# EEZ_AUX_PS_r4B41.net
KiCad netlist of a schematic drawn in EAGLE
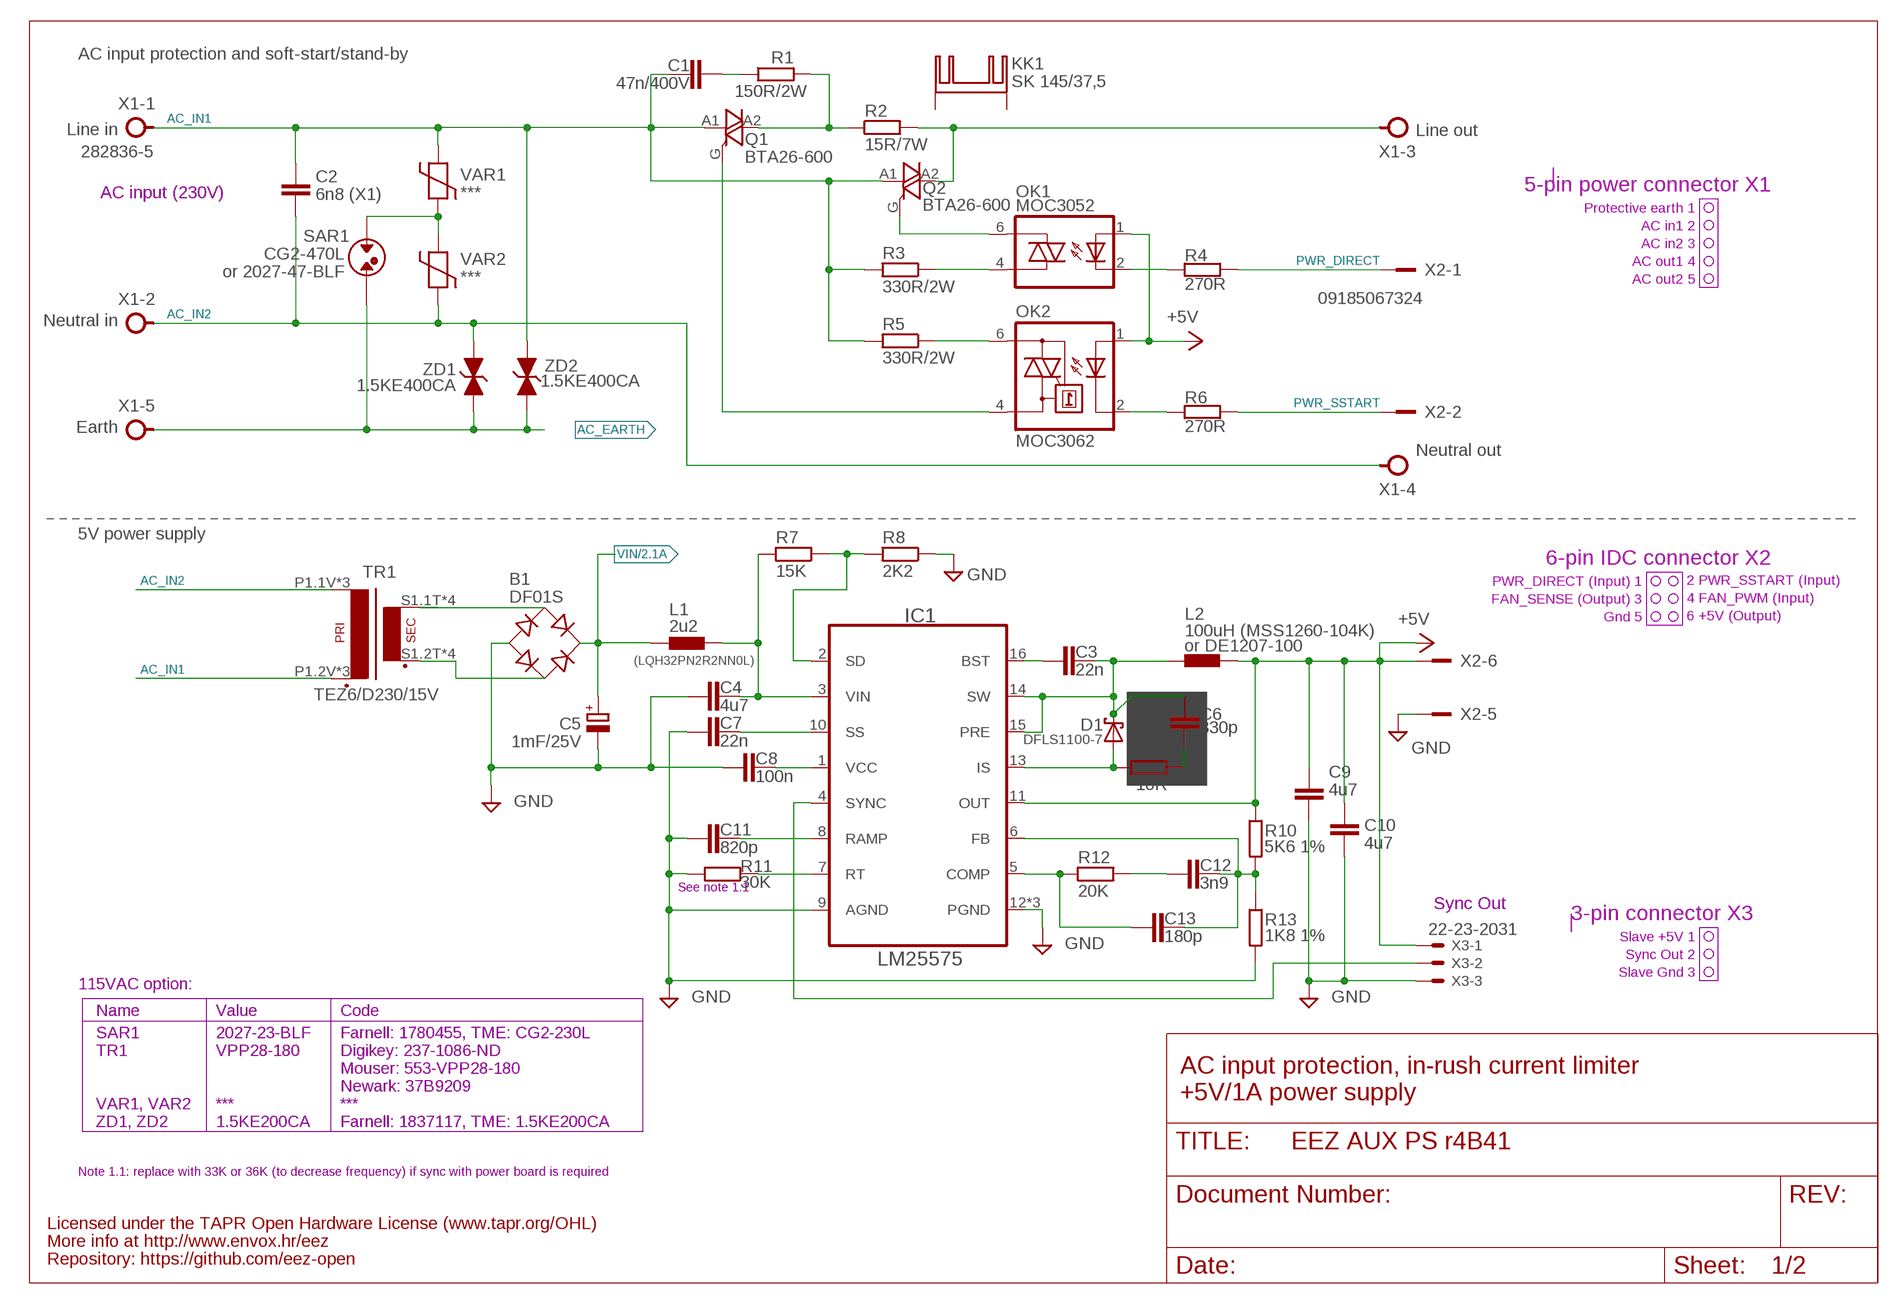
[diagram p0: schematic, sheet 1]
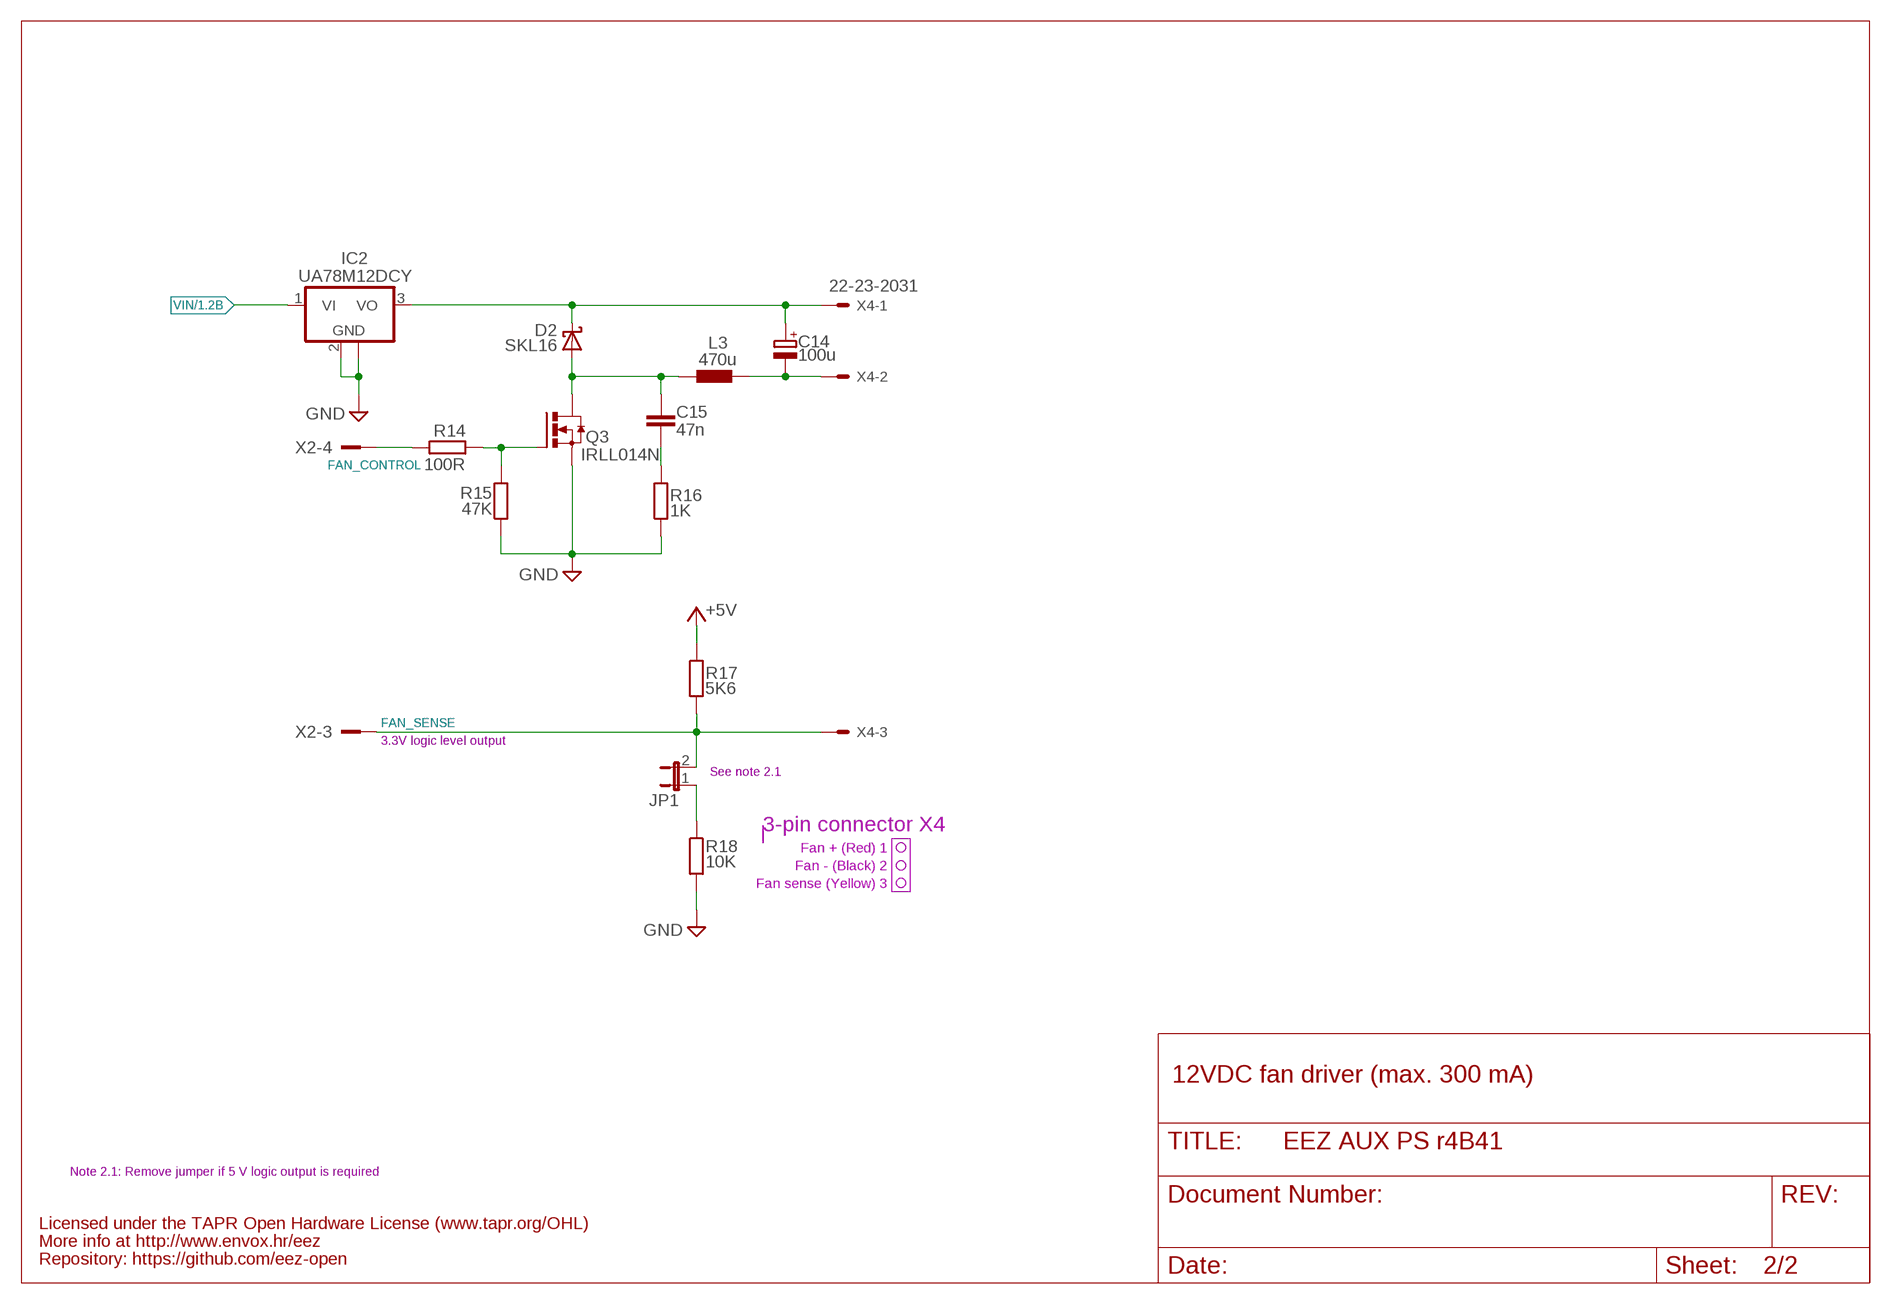
[diagram p1: schematic, sheet 2]

(export (version "E")
  (design (tool "Eeschema 10.0.6"))
  (components
    (comp (ref "C14")
      (value "100u")
      (footprint "eagle-import:CAPAE660X610N")
      (libsource (lib "eagle-import") (part "ECAPPANASONIC_H"))
    )
    (comp (ref "C15")
      (value "47n")
      (footprint "eagle-import:C0805")
      (libsource (lib "eagle-import") (part "C-EUC0805"))
    )
    (comp (ref "D2")
      (value "SKL16")
      (footprint "eagle-import:SOD123")
      (libsource (lib "eagle-import") (part "SCHOTTKYSOD123"))
    )
    (comp (ref "IC2")
      (value "UA78M12DCY")
      (footprint "eagle-import:SOT230P700X180-4N")
      (libsource (lib "eagle-import") (part "UA78MDCY"))
    )
    (comp (ref "JP1")
      (value "JP1E")
      (footprint "eagle-import:JP1")
      (libsource (lib "eagle-import") (part "JP1E"))
    )
    (comp (ref "L3")
      (value "470u")
      (footprint "eagle-import:DE0704")
      (libsource (lib "eagle-import") (part "DE0704"))
    )
    (comp (ref "Q3")
      (value "IRLL014N")
      (footprint "eagle-import:SOT223")
      (libsource (lib "eagle-import") (part "N-HEXFET-2D_?-SOT232IRLL014N"))
    )
    (comp (ref "R14")
      (value "100R")
      (footprint "eagle-import:R0805")
      (libsource (lib "eagle-import") (part "R-EU_R0805"))
    )
    (comp (ref "R15")
      (value "47K")
      (footprint "eagle-import:R0805")
      (libsource (lib "eagle-import") (part "R-EU_R0805"))
    )
    (comp (ref "R16")
      (value "1K")
      (footprint "eagle-import:R0805")
      (libsource (lib "eagle-import") (part "R-EU_R0805"))
    )
    (comp (ref "R17")
      (value "5K6")
      (footprint "eagle-import:R0805")
      (libsource (lib "eagle-import") (part "R-EU_R0805"))
    )
    (comp (ref "R18")
      (value "10K")
      (footprint "eagle-import:R0805")
      (libsource (lib "eagle-import") (part "R-EU_R0805"))
    )
    (comp (ref "X2")
      (value "09185067324")
      (footprint "eagle-import:IDC-6PIN")
      (libsource (lib "eagle-import") (part "IDC-6PIN"))
    )
    (comp (ref "X4")
      (value "22-23-2031")
      (footprint "eagle-import:22-23-2031")
      (fields (field (name "MF") "MOLEX"))
      (libsource (lib "eagle-import") (part "22-23-2031"))
    )
    (comp (ref "B1")
      (value "DF01S")
      (footprint "eagle-import:DFS")
      (libsource (lib "eagle-import") (part "DFS01"))
    )
    (comp (ref "C1")
      (value "47n/400V")
      (footprint "eagle-import:C075-052X106")
      (libsource (lib "eagle-import") (part "C-EU075-052X106"))
    )
    (comp (ref "C2")
      (value "6n8 (X1)")
      (footprint "eagle-import:C102-064X133")
      (libsource (lib "eagle-import") (part "C-EU102-064X133"))
    )
    (comp (ref "C3")
      (value "22n")
      (footprint "eagle-import:C0805")
      (libsource (lib "eagle-import") (part "C-EUC0805"))
    )
    (comp (ref "C4")
      (value "4u7")
      (footprint "eagle-import:C1210")
      (libsource (lib "eagle-import") (part "C-EUC1210"))
    )
    (comp (ref "C5")
      (value "1mF/25V")
      (footprint "eagle-import:ECAP5_10.5")
      (libsource (lib "eagle-import") (part "ECAP5G_10.5MM"))
    )
    (comp (ref "C6")
      (value "330p")
      (footprint "eagle-import:C0805")
      (libsource (lib "eagle-import") (part "C-EUC0805"))
    )
    (comp (ref "C7")
      (value "22n")
      (footprint "eagle-import:C0805")
      (libsource (lib "eagle-import") (part "C-EUC0805"))
    )
    (comp (ref "C8")
      (value "100n")
      (footprint "eagle-import:C0805")
      (libsource (lib "eagle-import") (part "C-EUC0805"))
    )
    (comp (ref "C9")
      (value "4u7")
      (footprint "eagle-import:C1210")
      (libsource (lib "eagle-import") (part "C-EUC1210"))
    )
    (comp (ref "C10")
      (value "4u7")
      (footprint "eagle-import:C1210")
      (libsource (lib "eagle-import") (part "C-EUC1210"))
    )
    (comp (ref "C11")
      (value "820p")
      (footprint "eagle-import:C0805")
      (libsource (lib "eagle-import") (part "C-EUC0805"))
    )
    (comp (ref "C12")
      (value "3n9")
      (footprint "eagle-import:C0805")
      (libsource (lib "eagle-import") (part "C-EUC0805"))
    )
    (comp (ref "C13")
      (value "180p")
      (footprint "eagle-import:C0805")
      (libsource (lib "eagle-import") (part "C-EUC0805"))
    )
    (comp (ref "D1")
      (value "DFLS1100-7")
      (footprint "eagle-import:SOD123")
      (libsource (lib "eagle-import") (part "SCHOTTKYSOD123"))
    )
    (comp (ref "IC1")
      (value "LM25575")
      (footprint "eagle-import:SOP65P640X110-17N_HOLE")
      (libsource (lib "eagle-import") (part "LM(2)5575"))
    )
    (comp (ref "KK1")
      (value "SK 145/37,5")
      (footprint "eagle-import:SK145")
      (libsource (lib "eagle-import") (part "SK145"))
    )
    (comp (ref "L1")
      (value "2u2")
      (footprint "eagle-import:L1210")
      (libsource (lib "eagle-import") (part "L1210"))
    )
    (comp (ref "L2")
      (value "100uH (MSS1260-104K)")
      (footprint "eagle-import:MSS1278")
      (libsource (lib "eagle-import") (part "COILCRAFT_MSS1278"))
    )
    (comp (ref "OK1")
      (value "MOC3052")
      (footprint "eagle-import:DIL6-SMD")
      (libsource (lib "eagle-import") (part "MOC305X"))
    )
    (comp (ref "OK2")
      (value "MOC3062")
      (footprint "eagle-import:DIL6-SMD")
      (fields
        (field (name "MF") "FAIRCHILD SEMICONDUCTOR")
        (field (name "MPN") "MOC3033S-M")
        (field (name "MF_1") "FAIRCHILD SEMICONDUCTOR")
        (field (name "MPN_1") "MOC3033S-M")
        (field (name "OC_FARNELL") "unknown")
        (field (name "OC_NEWARK") "05C2878")
      )
      (libsource (lib "eagle-import") (part "MOC30S33"))
    )
    (comp (ref "Q1")
      (value "BTA26-600")
      (footprint "eagle-import:TOP3S-1")
      (libsource (lib "eagle-import") (part "BTA26-V"))
    )
    (comp (ref "Q2")
      (value "BTA26-600")
      (footprint "eagle-import:TOP3S-1")
      (libsource (lib "eagle-import") (part "BTA26-V"))
    )
    (comp (ref "R1")
      (value "150R/2W")
      (footprint "eagle-import:R2512")
      (libsource (lib "eagle-import") (part "R-EU_R2512"))
    )
    (comp (ref "R2")
      (value "15R/7W")
      (footprint "eagle-import:R_0913")
      (libsource (lib "eagle-import") (part "R_EU7W"))
    )
    (comp (ref "R3")
      (value "330R/2W")
      (footprint "eagle-import:R2512")
      (libsource (lib "eagle-import") (part "R-EU_R2512"))
    )
    (comp (ref "R4")
      (value "270R")
      (footprint "eagle-import:R0805")
      (libsource (lib "eagle-import") (part "R-EU_R0805"))
    )
    (comp (ref "R5")
      (value "330R/2W")
      (footprint "eagle-import:R2512")
      (libsource (lib "eagle-import") (part "R-EU_R2512"))
    )
    (comp (ref "R6")
      (value "270R")
      (footprint "eagle-import:R0805")
      (libsource (lib "eagle-import") (part "R-EU_R0805"))
    )
    (comp (ref "R7")
      (value "15K")
      (footprint "eagle-import:R0805")
      (libsource (lib "eagle-import") (part "R-EU_R0805"))
    )
    (comp (ref "R8")
      (value "2K2")
      (footprint "eagle-import:R0805")
      (libsource (lib "eagle-import") (part "R-EU_R0805"))
    )
    (comp (ref "R9")
      (value "10R")
      (footprint "eagle-import:R1206")
      (libsource (lib "eagle-import") (part "R-EU_R1206"))
    )
    (comp (ref "R10")
      (value "5K6 1%")
      (footprint "eagle-import:R0805")
      (libsource (lib "eagle-import") (part "R-EU_R0805"))
    )
    (comp (ref "R11")
      (value "30K")
      (footprint "eagle-import:R0805")
      (libsource (lib "eagle-import") (part "R-EU_R0805"))
    )
    (comp (ref "R12")
      (value "20K")
      (footprint "eagle-import:R0805")
      (libsource (lib "eagle-import") (part "R-EU_R0805"))
    )
    (comp (ref "R13")
      (value "1K8 1%")
      (footprint "eagle-import:R0805")
      (libsource (lib "eagle-import") (part "R-EU_R0805"))
    )
    (comp (ref "SAR1")
      (value "CG2-470L")
      (footprint "eagle-import:SAR")
      (libsource (lib "eagle-import") (part "SAR"))
    )
    (comp (ref "TR1")
      (value "TEZ6/D230/15V")
      (footprint "eagle-import:PCB_TRAFO6VA_TEZ+VPP")
      (libsource (lib "eagle-import") (part "PCB_TRAFO6VA_TEZ+VPP"))
    )
    (comp (ref "VAR1")
      (value "***")
      (footprint "eagle-import:VARISTOR")
      (libsource (lib "eagle-import") (part "VARISTOR"))
    )
    (comp (ref "VAR2")
      (value "***")
      (footprint "eagle-import:VARISTOR")
      (libsource (lib "eagle-import") (part "VARISTOR"))
    )
    (comp (ref "X1")
      (value "282836-5")
      (footprint "eagle-import:TBLOCK5.0_5")
      (libsource (lib "eagle-import") (part "TBLOCK5.0_5A"))
    )
    (comp (ref "X3")
      (value "22-23-2031")
      (footprint "eagle-import:22-23-2031")
      (fields (field (name "MF") "MOLEX"))
      (libsource (lib "eagle-import") (part "22-23-2031"))
    )
    (comp (ref "ZD1")
      (value "1.5KE400CA")
      (footprint "eagle-import:DO201-BIDIR")
      (libsource (lib "eagle-import") (part "1.5KE-BIDIR"))
    )
    (comp (ref "ZD2")
      (value "1.5KE400CA")
      (footprint "eagle-import:DO201-BIDIR")
      (libsource (lib "eagle-import") (part "1.5KE-BIDIR"))
    )
  )
  (nets
    (net (code "1") (name "+5V") (class "Default")
      (node (ref "C10") (pin "1") (pinfunction "1_1") (pintype "passive"))
      (node (ref "C9") (pin "1") (pinfunction "1_1") (pintype "passive"))
      (node (ref "IC1") (pin "11") (pinfunction "OUT_11") (pintype "output"))
      (node (ref "L2") (pin "2") (pinfunction "2_2") (pintype "passive"))
      (node (ref "OK1") (pin "1") (pinfunction "A_1") (pintype "passive"))
      (node (ref "OK2") (pin "1") (pinfunction "A_1") (pintype "passive"))
      (node (ref "R10") (pin "1") (pinfunction "1_1") (pintype "passive"))
      (node (ref "R17") (pin "1") (pinfunction "1_1") (pintype "passive"))
      (node (ref "X2") (pin "6") (pinfunction "1_6") (pintype "passive"))
      (node (ref "X3") (pin "1") (pinfunction "S_1") (pintype "passive"))
    )
    (net (code "2") (name "AC_EARTH") (class "Default")
      (node (ref "SAR1") (pin "P$2") (pinfunction "P$2_P$2") (pintype "bidirectional"))
      (node (ref "X1") (pin "5") (pinfunction "1_5") (pintype "bidirectional"))
      (node (ref "ZD1") (pin "C") (pinfunction "1_C") (pintype "passive"))
      (node (ref "ZD2") (pin "C") (pinfunction "1_C") (pintype "passive"))
    )
    (net (code "3") (name "AC_IN1") (class "Default")
      (node (ref "C1") (pin "2") (pinfunction "2_2") (pintype "passive"))
      (node (ref "C2") (pin "1") (pinfunction "1_1") (pintype "passive"))
      (node (ref "Q1") (pin "A1") (pinfunction "A1_A1") (pintype "passive"))
      (node (ref "Q2") (pin "A1") (pinfunction "A1_A1") (pintype "passive"))
      (node (ref "R3") (pin "2") (pinfunction "2_2") (pintype "passive"))
      (node (ref "R5") (pin "2") (pinfunction "2_2") (pintype "passive"))
      (node (ref "TR1") (pin "P1.2V") (pinfunction "P2_P1.2V") (pintype "passive"))
      (node (ref "TR1") (pin "P2.2V") (pinfunction "P2_P2.2V") (pintype "passive"))
      (node (ref "TR1") (pin "P2_TEZ") (pinfunction "P2_P2_TEZ") (pintype "passive"))
      (node (ref "VAR1") (pin "P$2") (pinfunction "P$2_P$2") (pintype "bidirectional"))
      (node (ref "X1") (pin "1") (pinfunction "1_1") (pintype "bidirectional"))
      (node (ref "ZD2") (pin "A") (pinfunction "2_A") (pintype "passive"))
    )
    (net (code "4") (name "AC_IN2") (class "Default")
      (node (ref "C2") (pin "2") (pinfunction "2_2") (pintype "passive"))
      (node (ref "TR1") (pin "P1.1V") (pinfunction "P1_P1.1V") (pintype "passive"))
      (node (ref "TR1") (pin "P1_TEZ") (pinfunction "P1_P1_TEZ") (pintype "passive"))
      (node (ref "TR1") (pin "P2.1V") (pinfunction "P1_P2.1V") (pintype "passive"))
      (node (ref "VAR2") (pin "P$1") (pinfunction "P$1_P$1") (pintype "bidirectional"))
      (node (ref "X1") (pin "2") (pinfunction "1_2") (pintype "bidirectional"))
      (node (ref "X1") (pin "4") (pinfunction "1_4") (pintype "bidirectional"))
      (node (ref "ZD1") (pin "A") (pinfunction "2_A") (pintype "passive"))
    )
    (net (code "5") (name "FAN_CONTROL") (class "Default")
      (node (ref "R14") (pin "2") (pinfunction "2_2") (pintype "passive"))
      (node (ref "X2") (pin "4") (pinfunction "1_4") (pintype "passive"))
    )
    (net (code "6") (name "FAN_SENSE") (class "Default")
      (node (ref "JP1") (pin "2") (pinfunction "2_2") (pintype "passive"))
      (node (ref "R17") (pin "2") (pinfunction "2_2") (pintype "passive"))
      (node (ref "X2") (pin "3") (pinfunction "1_3") (pintype "passive"))
      (node (ref "X4") (pin "3") (pinfunction "S_3") (pintype "passive"))
    )
    (net (code "7") (name "GND") (class "Default")
      (node (ref "B1") (pin "-") (pinfunction "-_-") (pintype "passive"))
      (node (ref "C10") (pin "2") (pinfunction "2_2") (pintype "passive"))
      (node (ref "C11") (pin "1") (pinfunction "1_1") (pintype "passive"))
      (node (ref "C4") (pin "2") (pinfunction "2_2") (pintype "passive"))
      (node (ref "C5") (pin "-") (pinfunction "-_-") (pintype "passive"))
      (node (ref "C7") (pin "2") (pinfunction "2_2") (pintype "passive"))
      (node (ref "C8") (pin "1") (pinfunction "1_1") (pintype "passive"))
      (node (ref "C9") (pin "2") (pinfunction "2_2") (pintype "passive"))
      (node (ref "IC1") (pin "12") (pinfunction "PGND_12") (pintype "passive"))
      (node (ref "IC1") (pin "9") (pinfunction "AGND_9") (pintype "passive"))
      (node (ref "IC1") (pin "TP") (pinfunction "PGND_TP") (pintype "passive"))
      (node (ref "IC1") (pin "TP2") (pinfunction "PGND_TP2") (pintype "passive"))
      (node (ref "IC2") (pin "2") (pinfunction "GND_2") (pintype "passive"))
      (node (ref "IC2") (pin "4") (pinfunction "GND_4") (pintype "passive"))
      (node (ref "Q3") (pin "3") (pinfunction "S_3") (pintype "passive"))
      (node (ref "R11") (pin "2") (pinfunction "2_2") (pintype "passive"))
      (node (ref "R13") (pin "2") (pinfunction "2_2") (pintype "passive"))
      (node (ref "R15") (pin "1") (pinfunction "1_1") (pintype "passive"))
      (node (ref "R16") (pin "1") (pinfunction "1_1") (pintype "passive"))
      (node (ref "R18") (pin "2") (pinfunction "2_2") (pintype "passive"))
      (node (ref "R8") (pin "1") (pinfunction "1_1") (pintype "passive"))
      (node (ref "X2") (pin "5") (pinfunction "1_5") (pintype "passive"))
      (node (ref "X3") (pin "3") (pinfunction "S_3") (pintype "passive"))
    )
    (net (code "8") (name "Net-(B1-PadAC1)") (class "Default")
      (node (ref "B1") (pin "AC1") (pinfunction "AC1_AC1") (pintype "passive"))
      (node (ref "TR1") (pin "S1.1T") (pinfunction "S1_S1.1T") (pintype "passive"))
      (node (ref "TR1") (pin "S1.1V") (pinfunction "S1_S1.1V") (pintype "passive"))
      (node (ref "TR1") (pin "S2.1T") (pinfunction "S1_S2.1T") (pintype "passive"))
      (node (ref "TR1") (pin "S2.1V") (pinfunction "S1_S2.1V") (pintype "passive"))
    )
    (net (code "9") (name "Net-(B1-PadAC2)") (class "Default")
      (node (ref "B1") (pin "AC2") (pinfunction "AC2_AC2") (pintype "passive"))
      (node (ref "TR1") (pin "S1.2T") (pinfunction "S2_S1.2T") (pintype "passive"))
      (node (ref "TR1") (pin "S1.2V") (pinfunction "S2_S1.2V") (pintype "passive"))
      (node (ref "TR1") (pin "S2.2T") (pinfunction "S2_S2.2T") (pintype "passive"))
      (node (ref "TR1") (pin "S2.2V") (pinfunction "S2_S2.2V") (pintype "passive"))
    )
    (net (code "10") (name "Net-(C1-Pad1)") (class "Default")
      (node (ref "C1") (pin "1") (pinfunction "1_1") (pintype "passive"))
      (node (ref "R1") (pin "1") (pinfunction "1_1") (pintype "passive"))
    )
    (net (code "11") (name "Net-(C6-Pad2)") (class "Default")
      (node (ref "C6") (pin "2") (pinfunction "2_2") (pintype "passive"))
      (node (ref "R9") (pin "2") (pinfunction "2_2") (pintype "passive"))
    )
    (net (code "12") (name "Net-(C12-Pad2)") (class "Default")
      (node (ref "C12") (pin "2") (pinfunction "2_2") (pintype "passive"))
      (node (ref "R12") (pin "2") (pinfunction "2_2") (pintype "passive"))
    )
    (net (code "13") (name "Net-(C14-+)") (class "Default")
      (node (ref "C14") (pin "1") (pinfunction "+_1") (pintype "passive"))
      (node (ref "D2") (pin "C") (pinfunction "C_C") (pintype "passive"))
      (node (ref "IC2") (pin "3") (pinfunction "VO_3") (pintype "passive"))
      (node (ref "X4") (pin "1") (pinfunction "S_1") (pintype "passive"))
    )
    (net (code "14") (name "Net-(C14--)") (class "Default")
      (node (ref "C14") (pin "2") (pinfunction "-_2") (pintype "passive"))
      (node (ref "L3") (pin "1") (pinfunction "1_1") (pintype "passive"))
      (node (ref "X4") (pin "2") (pinfunction "S_2") (pintype "passive"))
    )
    (net (code "15") (name "Net-(C15-Pad1)") (class "Default")
      (node (ref "C15") (pin "1") (pinfunction "1_1") (pintype "passive"))
      (node (ref "R16") (pin "2") (pinfunction "2_2") (pintype "passive"))
    )
    (net (code "16") (name "Net-(C15-Pad2)") (class "Default")
      (node (ref "C15") (pin "2") (pinfunction "2_2") (pintype "passive"))
      (node (ref "D2") (pin "A") (pinfunction "A_A") (pintype "passive"))
      (node (ref "L3") (pin "2") (pinfunction "2_2") (pintype "passive"))
      (node (ref "Q3") (pin "2") (pinfunction "D_2") (pintype "passive"))
      (node (ref "Q3") (pin "4") (pinfunction "D_4") (pintype "passive"))
    )
    (net (code "17") (name "Net-(IC1-BST)") (class "Default")
      (node (ref "C3") (pin "2") (pinfunction "2_2") (pintype "passive"))
      (node (ref "IC1") (pin "16") (pinfunction "BST_16") (pintype "input"))
    )
    (net (code "18") (name "Net-(IC1-COMP)") (class "Default")
      (node (ref "C13") (pin "2") (pinfunction "2_2") (pintype "passive"))
      (node (ref "IC1") (pin "5") (pinfunction "COMP_5") (pintype "input"))
      (node (ref "R12") (pin "1") (pinfunction "1_1") (pintype "passive"))
    )
    (net (code "19") (name "Net-(IC1-FB)") (class "Default")
      (node (ref "C12") (pin "1") (pinfunction "1_1") (pintype "passive"))
      (node (ref "C13") (pin "1") (pinfunction "1_1") (pintype "passive"))
      (node (ref "IC1") (pin "6") (pinfunction "FB_6") (pintype "input"))
      (node (ref "R10") (pin "2") (pinfunction "2_2") (pintype "passive"))
      (node (ref "R13") (pin "1") (pinfunction "1_1") (pintype "passive"))
    )
    (net (code "20") (name "Net-(IC1-IS)") (class "Default")
      (node (ref "D1") (pin "A") (pinfunction "A_A") (pintype "passive"))
      (node (ref "IC1") (pin "13") (pinfunction "IS_13") (pintype "input"))
      (node (ref "R9") (pin "1") (pinfunction "1_1") (pintype "passive"))
    )
    (net (code "21") (name "Net-(IC1-PRE)") (class "Default")
      (node (ref "C3") (pin "1") (pinfunction "1_1") (pintype "passive"))
      (node (ref "C6") (pin "1") (pinfunction "1_1") (pintype "passive"))
      (node (ref "D1") (pin "C") (pinfunction "C_C") (pintype "passive"))
      (node (ref "IC1") (pin "14") (pinfunction "SW_14") (pintype "output"))
      (node (ref "IC1") (pin "15") (pinfunction "PRE_15") (pintype "input"))
      (node (ref "L2") (pin "1") (pinfunction "1_1") (pintype "passive"))
    )
    (net (code "22") (name "Net-(IC1-RAMP)") (class "Default")
      (node (ref "C11") (pin "2") (pinfunction "2_2") (pintype "passive"))
      (node (ref "IC1") (pin "8") (pinfunction "RAMP_8") (pintype "input"))
    )
    (net (code "23") (name "Net-(IC1-RT)") (class "Default")
      (node (ref "IC1") (pin "7") (pinfunction "RT_7") (pintype "input"))
      (node (ref "R11") (pin "1") (pinfunction "1_1") (pintype "passive"))
    )
    (net (code "24") (name "Net-(IC1-SD)") (class "Default")
      (node (ref "IC1") (pin "2") (pinfunction "SD_2") (pintype "input"))
      (node (ref "R7") (pin "1") (pinfunction "1_1") (pintype "passive"))
      (node (ref "R8") (pin "2") (pinfunction "2_2") (pintype "passive"))
    )
    (net (code "25") (name "Net-(IC1-SS)") (class "Default")
      (node (ref "C7") (pin "1") (pinfunction "1_1") (pintype "passive"))
      (node (ref "IC1") (pin "10") (pinfunction "SS_10") (pintype "input"))
    )
    (net (code "26") (name "Net-(IC1-SYNC)") (class "Default")
      (node (ref "IC1") (pin "4") (pinfunction "SYNC_4") (pintype "input"))
      (node (ref "X3") (pin "2") (pinfunction "S_2") (pintype "passive"))
    )
    (net (code "27") (name "Net-(IC1-VCC)") (class "Default")
      (node (ref "C8") (pin "2") (pinfunction "2_2") (pintype "passive"))
      (node (ref "IC1") (pin "1") (pinfunction "VCC_1") (pintype "power_in"))
    )
    (net (code "28") (name "Net-(IC1-VIN)") (class "Default")
      (node (ref "C4") (pin "1") (pinfunction "1_1") (pintype "passive"))
      (node (ref "IC1") (pin "3") (pinfunction "VIN_3") (pintype "input"))
      (node (ref "L1") (pin "2") (pinfunction "2_2") (pintype "passive"))
      (node (ref "R7") (pin "2") (pinfunction "2_2") (pintype "passive"))
    )
    (net (code "29") (name "Net-(JP1-Pad1)") (class "Default")
      (node (ref "JP1") (pin "1") (pinfunction "1_1") (pintype "passive"))
      (node (ref "R18") (pin "1") (pinfunction "1_1") (pintype "passive"))
    )
    (net (code "30") (name "Net-(OK1-A1)") (class "Default")
      (node (ref "OK1") (pin "4") (pinfunction "A1_4") (pintype "passive"))
      (node (ref "R3") (pin "1") (pinfunction "1_1") (pintype "passive"))
    )
    (net (code "31") (name "Net-(OK1-A2)") (class "Default")
      (node (ref "OK1") (pin "6") (pinfunction "A2_6") (pintype "passive"))
      (node (ref "Q2") (pin "G") (pinfunction "G_G") (pintype "passive"))
    )
    (net (code "32") (name "Net-(OK1-C)") (class "Default")
      (node (ref "OK1") (pin "2") (pinfunction "C_2") (pintype "passive"))
      (node (ref "R4") (pin "1") (pinfunction "1_1") (pintype "passive"))
    )
    (net (code "33") (name "Net-(OK2-A1)") (class "Default")
      (node (ref "OK2") (pin "4") (pinfunction "A1_4") (pintype "passive"))
      (node (ref "Q1") (pin "G") (pinfunction "G_G") (pintype "passive"))
    )
    (net (code "34") (name "Net-(OK2-A2)") (class "Default")
      (node (ref "OK2") (pin "6") (pinfunction "A2_6") (pintype "passive"))
      (node (ref "R5") (pin "1") (pinfunction "1_1") (pintype "passive"))
    )
    (net (code "35") (name "Net-(OK2-C)") (class "Default")
      (node (ref "OK2") (pin "2") (pinfunction "C_2") (pintype "passive"))
      (node (ref "R6") (pin "1") (pinfunction "1_1") (pintype "passive"))
    )
    (net (code "36") (name "Net-(Q1-PadA2)") (class "Default")
      (node (ref "Q1") (pin "A2") (pinfunction "A2_A2") (pintype "passive"))
      (node (ref "R1") (pin "2") (pinfunction "2_2") (pintype "passive"))
      (node (ref "R2") (pin "1") (pinfunction "1_1") (pintype "passive"))
    )
    (net (code "37") (name "Net-(Q3-G)") (class "Default")
      (node (ref "Q3") (pin "1") (pinfunction "G_1") (pintype "passive"))
      (node (ref "R14") (pin "1") (pinfunction "1_1") (pintype "passive"))
      (node (ref "R15") (pin "2") (pinfunction "2_2") (pintype "passive"))
    )
    (net (code "38") (name "Net-(SAR1-PadP$1)") (class "Default")
      (node (ref "SAR1") (pin "P$1") (pinfunction "P$1_P$1") (pintype "bidirectional"))
      (node (ref "VAR1") (pin "P$1") (pinfunction "P$1_P$1") (pintype "bidirectional"))
      (node (ref "VAR2") (pin "P$2") (pinfunction "P$2_P$2") (pintype "bidirectional"))
    )
    (net (code "39") (name "Net-(X1C-1)") (class "Default")
      (node (ref "Q2") (pin "A2") (pinfunction "A2_A2") (pintype "passive"))
      (node (ref "R2") (pin "2") (pinfunction "2_2") (pintype "passive"))
      (node (ref "X1") (pin "3") (pinfunction "1_3") (pintype "bidirectional"))
    )
    (net (code "40") (name "PWR_DIRECT") (class "Default")
      (node (ref "R4") (pin "2") (pinfunction "2_2") (pintype "passive"))
      (node (ref "X2") (pin "1") (pinfunction "1_1") (pintype "passive"))
    )
    (net (code "41") (name "PWR_SSTART") (class "Default")
      (node (ref "R6") (pin "2") (pinfunction "2_2") (pintype "passive"))
      (node (ref "X2") (pin "2") (pinfunction "1_2") (pintype "passive"))
    )
    (net (code "42") (name "VIN") (class "Default")
      (node (ref "B1") (pin "+") (pinfunction "+_+") (pintype "passive"))
      (node (ref "C5") (pin "+") (pinfunction "+_+") (pintype "passive"))
      (node (ref "IC2") (pin "1") (pinfunction "VI_1") (pintype "input"))
      (node (ref "L1") (pin "1") (pinfunction "1_1") (pintype "passive"))
    )
    (net (code "43") (name "unconnected-(KK1-K-Pad1)") (class "Default")
      (node (ref "KK1") (pin "1") (pinfunction "K_1") (pintype "passive"))
    )
    (net (code "44") (name "unconnected-(KK1-K-Pad2)") (class "Default")
      (node (ref "KK1") (pin "2") (pinfunction "K_2") (pintype "passive"))
    )
  )
)
